# Sensor_Board_0x04_Luminosity_TSL2561_v2.net
KiCad netlist of a schematic drawn in EAGLE
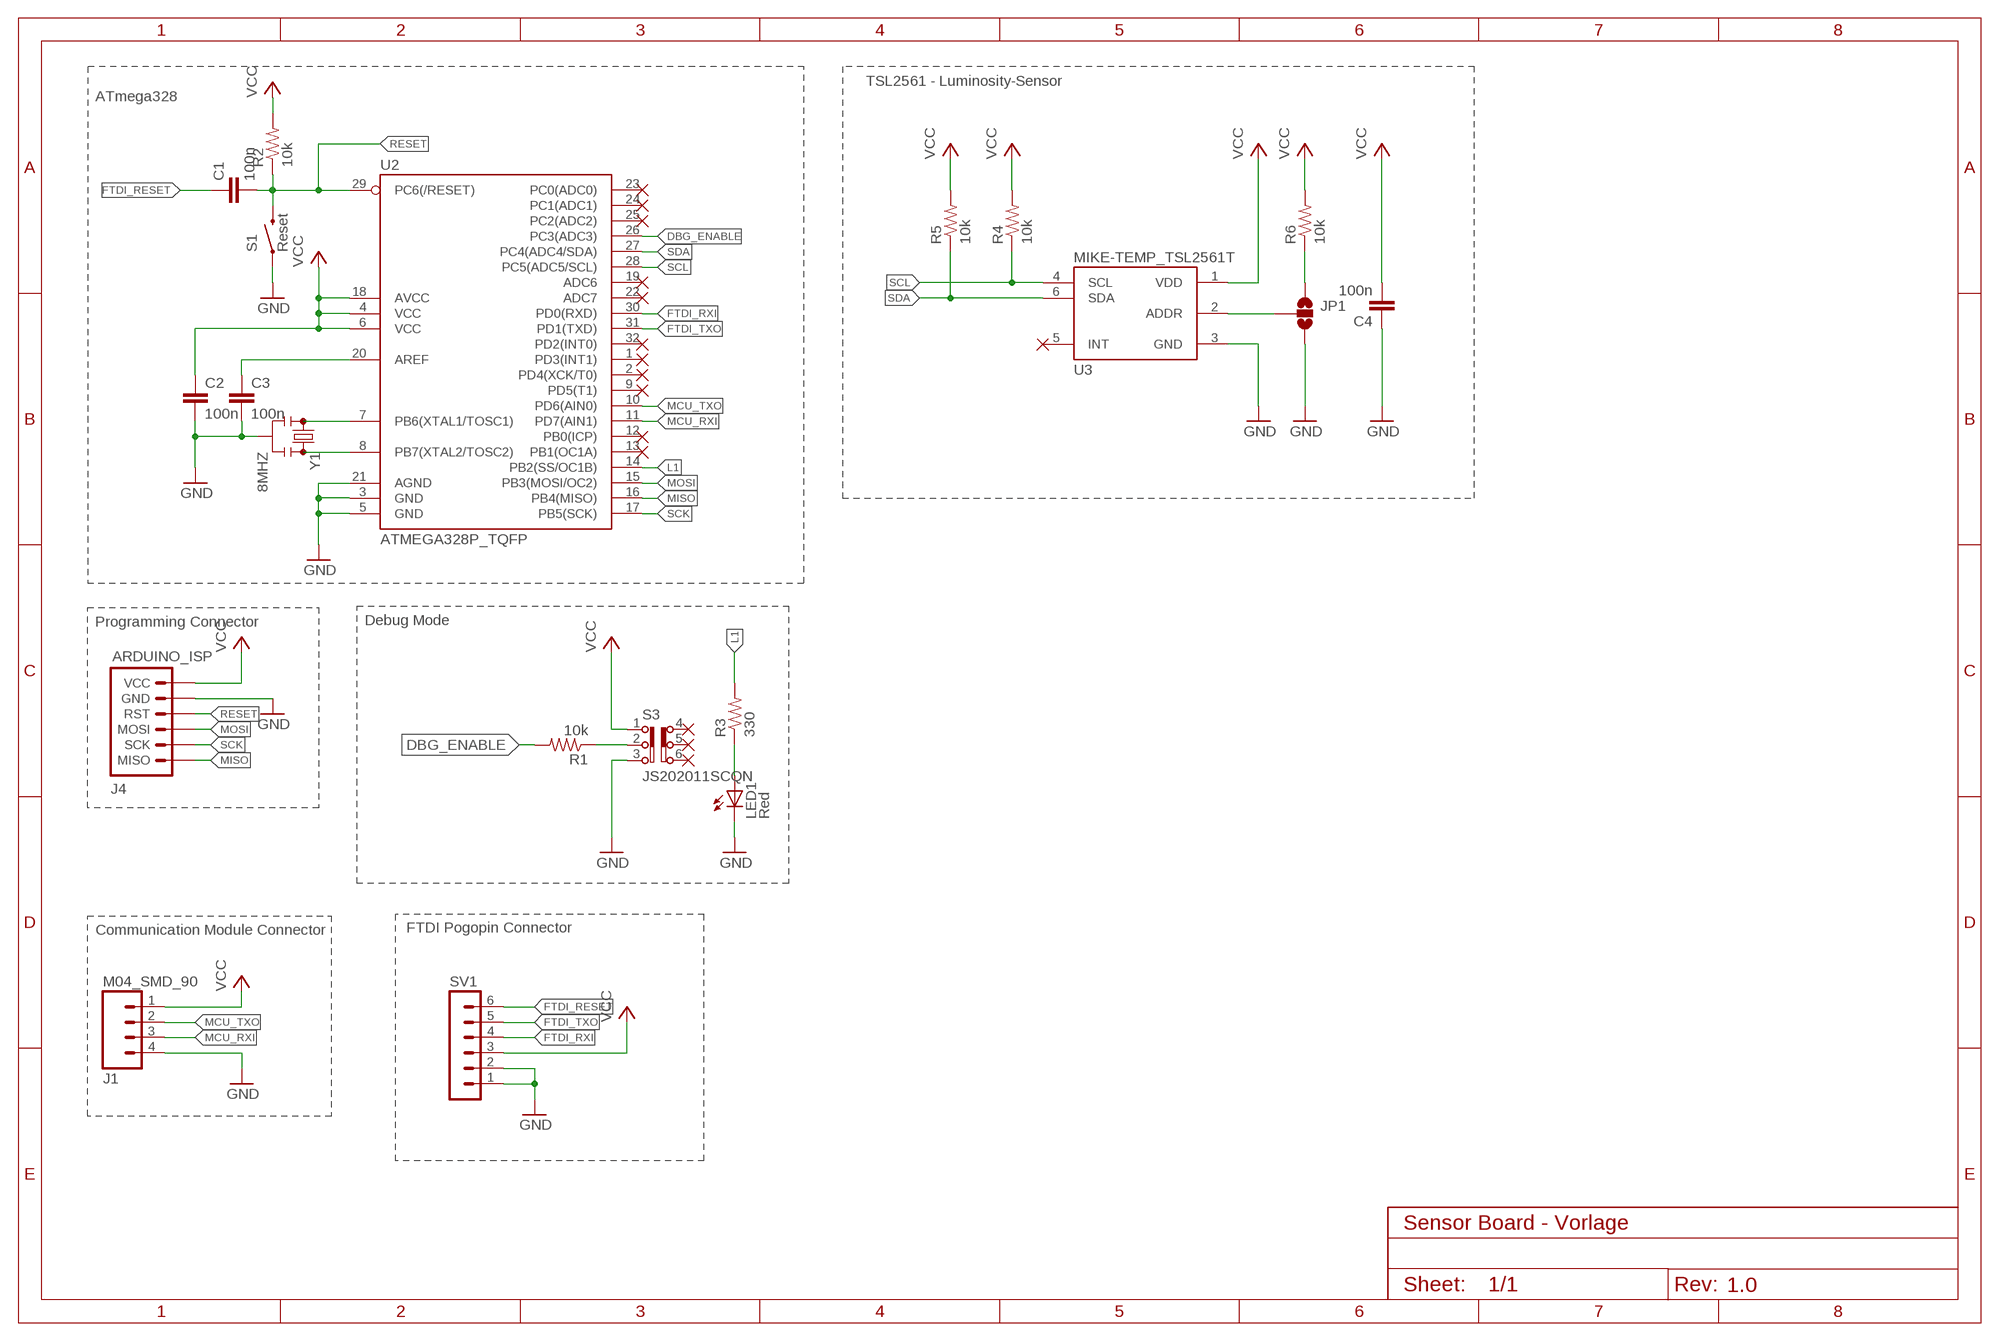
[diagram p0: schematic, sheet 1]

(export (version "E")
  (design (tool "Eeschema 10.0.6"))
  (components
    (comp (ref "C1")
      (value "100n")
      (footprint "eagle-import:C0805")
      (libsource (lib "eagle-import") (part "C"))
    )
    (comp (ref "C2")
      (value "100n")
      (footprint "eagle-import:C0805")
      (libsource (lib "eagle-import") (part "C"))
    )
    (comp (ref "C3")
      (value "100n")
      (footprint "eagle-import:C0805")
      (libsource (lib "eagle-import") (part "C"))
    )
    (comp (ref "C4")
      (value "100n")
      (footprint "eagle-import:C0805")
      (libsource (lib "eagle-import") (part "C"))
    )
    (comp (ref "J1")
      (value "M04_SMD_90")
      (footprint "eagle-import:M04_SMD_90")
      (libsource (lib "eagle-import") (part "M04_SMD_90"))
    )
    (comp (ref "J4")
      (value "ARDUINO_ISP")
      (footprint "eagle-import:M-2X3")
      (libsource (lib "eagle-import") (part "ARDUINO_ISP"))
    )
    (comp (ref "JP1")
      (value "MIKE-TEMP_SOLDERJUMPER_2WAYS")
      (footprint "eagle-import:MIKE-TEMP_SJ_3")
      (libsource (lib "eagle-import") (part "MIKE-TEMP_SOLDERJUMPER_2WAYS"))
    )
    (comp (ref "LED1")
      (value "Red")
      (footprint "eagle-import:SML0805")
      (libsource (lib "eagle-import") (part "LEDSML0805"))
    )
    (comp (ref "R1")
      (value "10k")
      (footprint "eagle-import:0805")
      (libsource (lib "eagle-import") (part "RESISTOR0805-RES"))
    )
    (comp (ref "R2")
      (value "10k")
      (footprint "eagle-import:0805")
      (libsource (lib "eagle-import") (part "RESISTOR0805-RES"))
    )
    (comp (ref "R3")
      (value "330")
      (footprint "eagle-import:0805")
      (libsource (lib "eagle-import") (part "RESISTOR0805-RES"))
    )
    (comp (ref "R4")
      (value "10k")
      (footprint "eagle-import:0805")
      (libsource (lib "eagle-import") (part "RESISTOR0805-RES"))
    )
    (comp (ref "R5")
      (value "10k")
      (footprint "eagle-import:0805")
      (libsource (lib "eagle-import") (part "RESISTOR0805-RES"))
    )
    (comp (ref "R6")
      (value "10k")
      (footprint "eagle-import:0805")
      (libsource (lib "eagle-import") (part "RESISTOR0805-RES"))
    )
    (comp (ref "S1")
      (value "Reset")
      (footprint "eagle-import:M-PUSHBUTTON-SMD")
      (libsource (lib "eagle-import") (part "PUSHBUTTON"))
    )
    (comp (ref "S3")
      (value "JS202011SCQN")
      (footprint "eagle-import:JS202011SCQN")
      (libsource (lib "eagle-import") (part "JS202011SCQN"))
    )
    (comp (ref "SV1")
      (value "MA06-1")
      (footprint "eagle-import:MA06-1")
      (libsource (lib "eagle-import") (part "MA06-1"))
    )
    (comp (ref "U2")
      (value "ATMEGA328P_TQFP")
      (footprint "eagle-import:TQFP32-08")
      (libsource (lib "eagle-import") (part "ATMEGA328P_TQFP"))
    )
    (comp (ref "U3")
      (value "MIKE-TEMP_TSL2561T")
      (footprint "eagle-import:MIKE-TEMP_TMB-6")
      (libsource (lib "eagle-import") (part "MIKE-TEMP_TSL2561T"))
    )
    (comp (ref "Y1")
      (value "8MHZ")
      (footprint "eagle-import:RESONATOR-SMD")
      (libsource (lib "eagle-import") (part "RESONATOR8MHZ"))
    )
  )
  (nets
    (net (code "1") (name "DBG_ENABLE") (class "Default")
      (node (ref "R1") (pin "2") (pinfunction "2_2") (pintype "passive"))
      (node (ref "U2") (pin "26") (pinfunction "PC3(ADC3)_26") (pintype "bidirectional"))
    )
    (net (code "2") (name "FTDI_RESET") (class "Default")
      (node (ref "C1") (pin "1") (pinfunction "1_1") (pintype "passive"))
      (node (ref "SV1") (pin "6") (pinfunction "6_6") (pintype "passive"))
    )
    (net (code "3") (name "FTDI_RXI") (class "Default")
      (node (ref "SV1") (pin "4") (pinfunction "4_4") (pintype "passive"))
      (node (ref "U2") (pin "30") (pinfunction "PD0(RXD)_30") (pintype "bidirectional"))
    )
    (net (code "4") (name "FTDI_TXO") (class "Default")
      (node (ref "SV1") (pin "5") (pinfunction "5_5") (pintype "passive"))
      (node (ref "U2") (pin "31") (pinfunction "PD1(TXD)_31") (pintype "bidirectional"))
    )
    (net (code "5") (name "GND") (class "Default")
      (node (ref "C2") (pin "2") (pinfunction "2_2") (pintype "passive"))
      (node (ref "C3") (pin "2") (pinfunction "2_2") (pintype "passive"))
      (node (ref "C4") (pin "1") (pinfunction "1_1") (pintype "passive"))
      (node (ref "J1") (pin "4") (pinfunction "4_4") (pintype "passive"))
      (node (ref "J4") (pin "P$5") (pinfunction "GND_P$5") (pintype "passive"))
      (node (ref "JP1") (pin "3") (pinfunction "3_3") (pintype "passive"))
      (node (ref "LED1") (pin "C") (pinfunction "C_C") (pintype "passive"))
      (node (ref "S1") (pin "1") (pinfunction "LEFT_1") (pintype "passive"))
      (node (ref "S1") (pin "2") (pinfunction "LEFT_2") (pintype "passive"))
      (node (ref "S3") (pin "3") (pinfunction "3_3") (pintype "passive"))
      (node (ref "SV1") (pin "1") (pinfunction "1_1") (pintype "passive"))
      (node (ref "SV1") (pin "2") (pinfunction "2_2") (pintype "passive"))
      (node (ref "U2") (pin "21") (pinfunction "AGND_21") (pintype "bidirectional"))
      (node (ref "U2") (pin "3") (pinfunction "GND_3") (pintype "bidirectional"))
      (node (ref "U2") (pin "5") (pinfunction "GND_5") (pintype "bidirectional"))
      (node (ref "U3") (pin "3") (pinfunction "GND_3") (pintype "power_in"))
      (node (ref "Y1") (pin "2") (pinfunction "2_2") (pintype "passive"))
    )
    (net (code "6") (name "L1") (class "Default")
      (node (ref "R3") (pin "2") (pinfunction "2_2") (pintype "passive"))
      (node (ref "U2") (pin "14") (pinfunction "PB2(SS/OC1B)_14") (pintype "bidirectional"))
    )
    (net (code "7") (name "MCU_RXI") (class "Default")
      (node (ref "J1") (pin "3") (pinfunction "3_3") (pintype "passive"))
      (node (ref "U2") (pin "11") (pinfunction "PD7(AIN1)_11") (pintype "bidirectional"))
    )
    (net (code "8") (name "MCU_TXO") (class "Default")
      (node (ref "J1") (pin "2") (pinfunction "2_2") (pintype "passive"))
      (node (ref "U2") (pin "10") (pinfunction "PD6(AIN0)_10") (pintype "bidirectional"))
    )
    (net (code "9") (name "MISO") (class "Default")
      (node (ref "J4") (pin "P$1") (pinfunction "MISO_P$1") (pintype "passive"))
      (node (ref "U2") (pin "16") (pinfunction "PB4(MISO)_16") (pintype "bidirectional"))
    )
    (net (code "10") (name "MOSI") (class "Default")
      (node (ref "J4") (pin "P$3") (pinfunction "MOSI_P$3") (pintype "passive"))
      (node (ref "U2") (pin "15") (pinfunction "PB3(MOSI/OC2)_15") (pintype "bidirectional"))
    )
    (net (code "11") (name "Net-(JP1-Pad1)") (class "Default")
      (node (ref "JP1") (pin "1") (pinfunction "1_1") (pintype "passive"))
      (node (ref "R6") (pin "1") (pinfunction "1_1") (pintype "passive"))
    )
    (net (code "12") (name "Net-(LED1-PadA)") (class "Default")
      (node (ref "LED1") (pin "A") (pinfunction "A_A") (pintype "passive"))
      (node (ref "R3") (pin "1") (pinfunction "1_1") (pintype "passive"))
    )
    (net (code "13") (name "Net-(R1-Pad1)") (class "Default")
      (node (ref "R1") (pin "1") (pinfunction "1_1") (pintype "passive"))
      (node (ref "S3") (pin "2") (pinfunction "2_2") (pintype "passive"))
    )
    (net (code "14") (name "Net-(U2-AREF)") (class "Default")
      (node (ref "C3") (pin "1") (pinfunction "1_1") (pintype "passive"))
      (node (ref "U2") (pin "20") (pinfunction "AREF_20") (pintype "bidirectional"))
    )
    (net (code "15") (name "Net-(U2-PB6(XTAL1{slash}TOSC1))") (class "Default")
      (node (ref "U2") (pin "7") (pinfunction "PB6(XTAL1/TOSC1)_7") (pintype "bidirectional"))
      (node (ref "Y1") (pin "1") (pinfunction "1_1") (pintype "passive"))
    )
    (net (code "16") (name "Net-(U2-PB7(XTAL2{slash}TOSC2))") (class "Default")
      (node (ref "U2") (pin "8") (pinfunction "PB7(XTAL2/TOSC2)_8") (pintype "bidirectional"))
      (node (ref "Y1") (pin "3") (pinfunction "3_3") (pintype "passive"))
    )
    (net (code "17") (name "Net-(U3-ADDR)") (class "Default")
      (node (ref "JP1") (pin "2") (pinfunction "2_2") (pintype "passive"))
      (node (ref "U3") (pin "2") (pinfunction "ADDR_2") (pintype "input"))
    )
    (net (code "18") (name "RESET") (class "Default")
      (node (ref "C1") (pin "2") (pinfunction "2_2") (pintype "passive"))
      (node (ref "J4") (pin "P$4") (pinfunction "RST_P$4") (pintype "passive"))
      (node (ref "R2") (pin "1") (pinfunction "1_1") (pintype "passive"))
      (node (ref "S1") (pin "3") (pinfunction "RIGHT_3") (pintype "passive"))
      (node (ref "S1") (pin "4") (pinfunction "RIGHT_4") (pintype "passive"))
      (node (ref "U2") (pin "29") (pinfunction "PC6(/RESET)_29") (pintype "bidirectional"))
    )
    (net (code "19") (name "SCK") (class "Default")
      (node (ref "J4") (pin "P$2") (pinfunction "SCK_P$2") (pintype "passive"))
      (node (ref "U2") (pin "17") (pinfunction "PB5(SCK)_17") (pintype "bidirectional"))
    )
    (net (code "20") (name "SCL") (class "Default")
      (node (ref "R4") (pin "1") (pinfunction "1_1") (pintype "passive"))
      (node (ref "U2") (pin "28") (pinfunction "PC5(ADC5/SCL)_28") (pintype "bidirectional"))
      (node (ref "U3") (pin "4") (pinfunction "SCL_4") (pintype "input"))
    )
    (net (code "21") (name "SDA") (class "Default")
      (node (ref "R5") (pin "1") (pinfunction "1_1") (pintype "passive"))
      (node (ref "U2") (pin "27") (pinfunction "PC4(ADC4/SDA)_27") (pintype "bidirectional"))
      (node (ref "U3") (pin "6") (pinfunction "SDA_6") (pintype "bidirectional"))
    )
    (net (code "22") (name "VCC") (class "Default")
      (node (ref "C2") (pin "1") (pinfunction "1_1") (pintype "passive"))
      (node (ref "C4") (pin "2") (pinfunction "2_2") (pintype "passive"))
      (node (ref "J1") (pin "1") (pinfunction "1_1") (pintype "passive"))
      (node (ref "J4") (pin "P$6") (pinfunction "VCC_P$6") (pintype "passive"))
      (node (ref "R2") (pin "2") (pinfunction "2_2") (pintype "passive"))
      (node (ref "R4") (pin "2") (pinfunction "2_2") (pintype "passive"))
      (node (ref "R5") (pin "2") (pinfunction "2_2") (pintype "passive"))
      (node (ref "R6") (pin "2") (pinfunction "2_2") (pintype "passive"))
      (node (ref "S3") (pin "1") (pinfunction "1_1") (pintype "passive"))
      (node (ref "SV1") (pin "3") (pinfunction "3_3") (pintype "passive"))
      (node (ref "U2") (pin "18") (pinfunction "AVCC_18") (pintype "bidirectional"))
      (node (ref "U2") (pin "4") (pinfunction "VCC_4") (pintype "bidirectional"))
      (node (ref "U2") (pin "6") (pinfunction "VCC_6") (pintype "bidirectional"))
      (node (ref "U3") (pin "1") (pinfunction "VDD_1") (pintype "power_in"))
    )
    (net (code "23") (name "unconnected-(S3-Pad4)") (class "Default")
      (node (ref "S3") (pin "4") (pinfunction "4_4") (pintype "passive"))
    )
    (net (code "24") (name "unconnected-(S3-Pad5)") (class "Default")
      (node (ref "S3") (pin "5") (pinfunction "5_5") (pintype "passive"))
    )
    (net (code "25") (name "unconnected-(S3-Pad6)") (class "Default")
      (node (ref "S3") (pin "6") (pinfunction "6_6") (pintype "passive"))
    )
    (net (code "26") (name "unconnected-(U2-ADC6-Pad19)") (class "Default")
      (node (ref "U2") (pin "19") (pinfunction "ADC6_19") (pintype "bidirectional"))
    )
    (net (code "27") (name "unconnected-(U2-ADC7-Pad22)") (class "Default")
      (node (ref "U2") (pin "22") (pinfunction "ADC7_22") (pintype "bidirectional"))
    )
    (net (code "28") (name "unconnected-(U2-PB0(ICP)-Pad12)") (class "Default")
      (node (ref "U2") (pin "12") (pinfunction "PB0(ICP)_12") (pintype "bidirectional"))
    )
    (net (code "29") (name "unconnected-(U2-PB1(OC1A)-Pad13)") (class "Default")
      (node (ref "U2") (pin "13") (pinfunction "PB1(OC1A)_13") (pintype "bidirectional"))
    )
    (net (code "30") (name "unconnected-(U2-PC0(ADC0)-Pad23)") (class "Default")
      (node (ref "U2") (pin "23") (pinfunction "PC0(ADC0)_23") (pintype "bidirectional"))
    )
    (net (code "31") (name "unconnected-(U2-PC1(ADC1)-Pad24)") (class "Default")
      (node (ref "U2") (pin "24") (pinfunction "PC1(ADC1)_24") (pintype "bidirectional"))
    )
    (net (code "32") (name "unconnected-(U2-PC2(ADC2)-Pad25)") (class "Default")
      (node (ref "U2") (pin "25") (pinfunction "PC2(ADC2)_25") (pintype "bidirectional"))
    )
    (net (code "33") (name "unconnected-(U2-PD2(INT0)-Pad32)") (class "Default")
      (node (ref "U2") (pin "32") (pinfunction "PD2(INT0)_32") (pintype "bidirectional"))
    )
    (net (code "34") (name "unconnected-(U2-PD3(INT1)-Pad1)") (class "Default")
      (node (ref "U2") (pin "1") (pinfunction "PD3(INT1)_1") (pintype "bidirectional"))
    )
    (net (code "35") (name "unconnected-(U2-PD4(XCK{slash}T0)-Pad2)") (class "Default")
      (node (ref "U2") (pin "2") (pinfunction "PD4(XCK/T0)_2") (pintype "bidirectional"))
    )
    (net (code "36") (name "unconnected-(U2-PD5(T1)-Pad9)") (class "Default")
      (node (ref "U2") (pin "9") (pinfunction "PD5(T1)_9") (pintype "bidirectional"))
    )
    (net (code "37") (name "unconnected-(U3-INT-Pad5)") (class "Default")
      (node (ref "U3") (pin "5") (pinfunction "INT_5") (pintype "output"))
    )
  )
)
